# bar_graph_meter_2in_clip_in_w_47uF.net
KiCad netlist of a schematic drawn in EAGLE
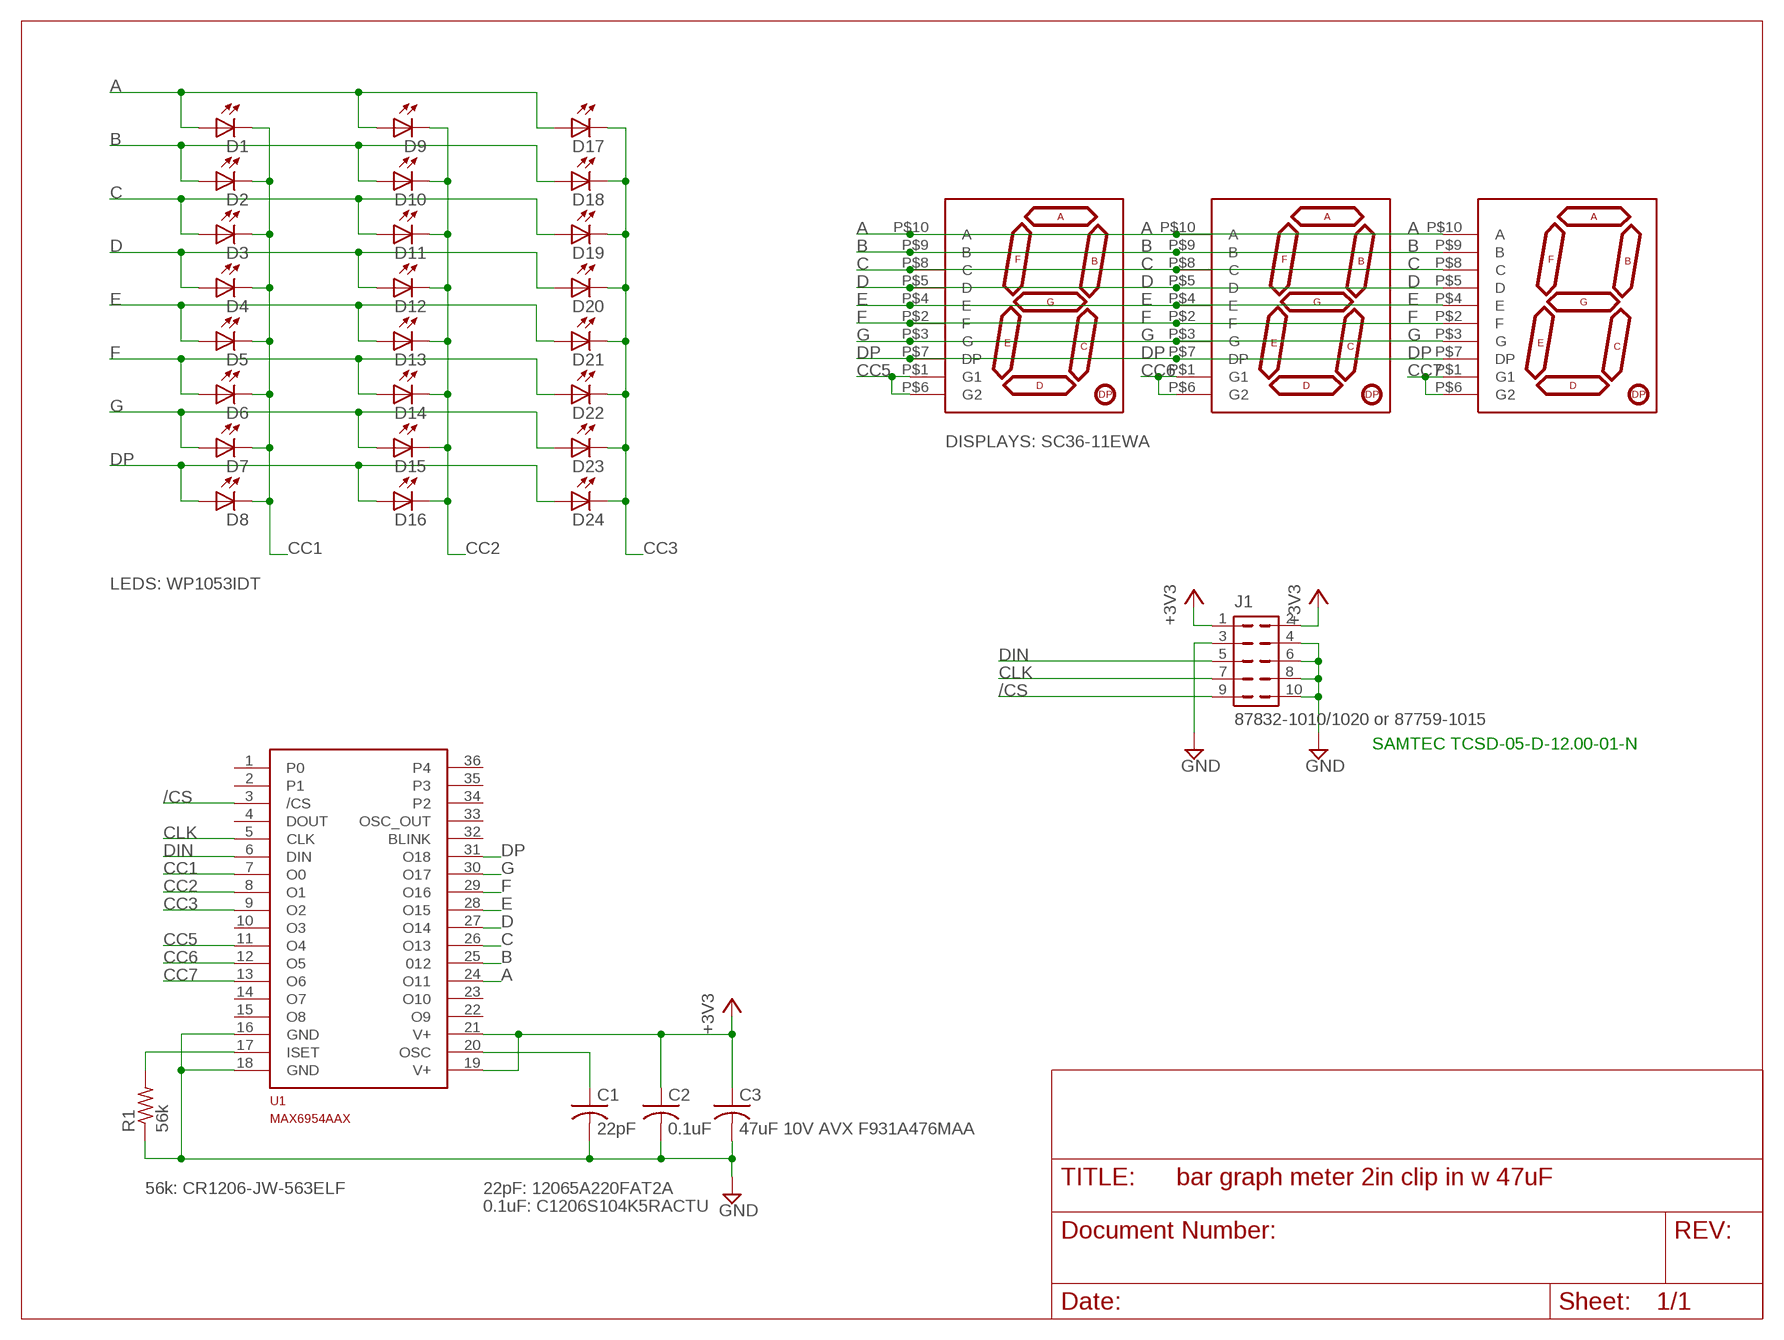
[diagram p0: schematic, sheet 1]

(export (version "E")
  (design (tool "Eeschema 10.0.6"))
  (components
    (comp (ref "C1")
      (value "22pF")
      (footprint "eagle-import:C1206")
      (libsource (lib "eagle-import") (part "C-USC1206"))
    )
    (comp (ref "C2")
      (value "0.1uF")
      (footprint "eagle-import:C1206")
      (libsource (lib "eagle-import") (part "C-USC1206"))
    )
    (comp (ref "C3")
      (value "47uF 10V AVX F931A476MAA")
      (footprint "eagle-import:C1206")
      (libsource (lib "eagle-import") (part "C-USC1206"))
    )
    (comp (ref "D1")
      (value "LEDSQR2X5")
      (footprint "eagle-import:LED2X5")
      (libsource (lib "eagle-import") (part "LEDSQR2X5"))
    )
    (comp (ref "D2")
      (value "LEDSQR2X5")
      (footprint "eagle-import:LED2X5")
      (libsource (lib "eagle-import") (part "LEDSQR2X5"))
    )
    (comp (ref "D3")
      (value "LEDSQR2X5")
      (footprint "eagle-import:LED2X5")
      (libsource (lib "eagle-import") (part "LEDSQR2X5"))
    )
    (comp (ref "D4")
      (value "LEDSQR2X5")
      (footprint "eagle-import:LED2X5")
      (libsource (lib "eagle-import") (part "LEDSQR2X5"))
    )
    (comp (ref "D5")
      (value "LEDSQR2X5")
      (footprint "eagle-import:LED2X5")
      (libsource (lib "eagle-import") (part "LEDSQR2X5"))
    )
    (comp (ref "D6")
      (value "LEDSQR2X5")
      (footprint "eagle-import:LED2X5")
      (libsource (lib "eagle-import") (part "LEDSQR2X5"))
    )
    (comp (ref "D7")
      (value "LEDSQR2X5")
      (footprint "eagle-import:LED2X5")
      (libsource (lib "eagle-import") (part "LEDSQR2X5"))
    )
    (comp (ref "D8")
      (value "LEDSQR2X5")
      (footprint "eagle-import:LED2X5")
      (libsource (lib "eagle-import") (part "LEDSQR2X5"))
    )
    (comp (ref "D9")
      (value "LEDSQR2X5")
      (footprint "eagle-import:LED2X5")
      (libsource (lib "eagle-import") (part "LEDSQR2X5"))
    )
    (comp (ref "D10")
      (value "LEDSQR2X5")
      (footprint "eagle-import:LED2X5")
      (libsource (lib "eagle-import") (part "LEDSQR2X5"))
    )
    (comp (ref "D11")
      (value "LEDSQR2X5")
      (footprint "eagle-import:LED2X5")
      (libsource (lib "eagle-import") (part "LEDSQR2X5"))
    )
    (comp (ref "D12")
      (value "LEDSQR2X5")
      (footprint "eagle-import:LED2X5")
      (libsource (lib "eagle-import") (part "LEDSQR2X5"))
    )
    (comp (ref "D13")
      (value "LEDSQR2X5")
      (footprint "eagle-import:LED2X5")
      (libsource (lib "eagle-import") (part "LEDSQR2X5"))
    )
    (comp (ref "D14")
      (value "LEDSQR2X5")
      (footprint "eagle-import:LED2X5")
      (libsource (lib "eagle-import") (part "LEDSQR2X5"))
    )
    (comp (ref "D15")
      (value "LEDSQR2X5")
      (footprint "eagle-import:LED2X5")
      (libsource (lib "eagle-import") (part "LEDSQR2X5"))
    )
    (comp (ref "D16")
      (value "LEDSQR2X5")
      (footprint "eagle-import:LED2X5")
      (libsource (lib "eagle-import") (part "LEDSQR2X5"))
    )
    (comp (ref "D17")
      (value "LEDSQR2X5")
      (footprint "eagle-import:LED2X5")
      (libsource (lib "eagle-import") (part "LEDSQR2X5"))
    )
    (comp (ref "D18")
      (value "LEDSQR2X5")
      (footprint "eagle-import:LED2X5")
      (libsource (lib "eagle-import") (part "LEDSQR2X5"))
    )
    (comp (ref "D19")
      (value "LEDSQR2X5")
      (footprint "eagle-import:LED2X5")
      (libsource (lib "eagle-import") (part "LEDSQR2X5"))
    )
    (comp (ref "D20")
      (value "LEDSQR2X5")
      (footprint "eagle-import:LED2X5")
      (libsource (lib "eagle-import") (part "LEDSQR2X5"))
    )
    (comp (ref "D21")
      (value "LEDSQR2X5")
      (footprint "eagle-import:LED2X5")
      (libsource (lib "eagle-import") (part "LEDSQR2X5"))
    )
    (comp (ref "D22")
      (value "LEDSQR2X5")
      (footprint "eagle-import:LED2X5")
      (libsource (lib "eagle-import") (part "LEDSQR2X5"))
    )
    (comp (ref "D23")
      (value "LEDSQR2X5")
      (footprint "eagle-import:LED2X5")
      (libsource (lib "eagle-import") (part "LEDSQR2X5"))
    )
    (comp (ref "D24")
      (value "LEDSQR2X5")
      (footprint "eagle-import:LED2X5")
      (libsource (lib "eagle-import") (part "LEDSQR2X5"))
    )
    (comp (ref "D25")
      (value "SC36-11EWA")
      (footprint "eagle-import:SA36-11")
      (libsource (lib "eagle-import") (part "SA36-11EWA"))
    )
    (comp (ref "D26")
      (value "SC36-11EWA")
      (footprint "eagle-import:SA36-11")
      (libsource (lib "eagle-import") (part "SA36-11EWA"))
    )
    (comp (ref "D27")
      (value "SC36-11EWA")
      (footprint "eagle-import:SA36-11")
      (libsource (lib "eagle-import") (part "SA36-11EWA"))
    )
    (comp (ref "J1")
      (value "87832-1010/1020 or 87759-1015")
      (footprint "eagle-import:87832-10")
      (libsource (lib "eagle-import") (part "87832-10"))
    )
    (comp (ref "R1")
      (value "56k")
      (footprint "eagle-import:R1206")
      (libsource (lib "eagle-import") (part "R-US_R1206"))
    )
    (comp (ref "U1")
      (value "MAX6954AAX")
      (footprint "eagle-import:MAXIM-0.8-SSOP36")
      (libsource (lib "eagle-import") (part "MAX6954AAX"))
    )
  )
  (nets
    (net (code "1") (name "+3V3") (class "Default")
      (node (ref "C2") (pin "1") (pinfunction "1_1") (pintype "passive"))
      (node (ref "C3") (pin "1") (pinfunction "1_1") (pintype "passive"))
      (node (ref "J1") (pin "1") (pinfunction "1_1") (pintype "passive"))
      (node (ref "J1") (pin "2") (pinfunction "2_2") (pintype "passive"))
      (node (ref "U1") (pin "19") (pinfunction "V+_19") (pintype "bidirectional"))
      (node (ref "U1") (pin "21") (pinfunction "V+_21") (pintype "bidirectional"))
    )
    (net (code "2") (name "/A") (class "Default")
      (node (ref "D1") (pin "A") (pinfunction "A_A") (pintype "passive"))
      (node (ref "D17") (pin "A") (pinfunction "A_A") (pintype "passive"))
      (node (ref "D25") (pin "P$10") (pinfunction "A_P$10") (pintype "bidirectional"))
      (node (ref "D26") (pin "P$10") (pinfunction "A_P$10") (pintype "bidirectional"))
      (node (ref "D27") (pin "P$10") (pinfunction "A_P$10") (pintype "bidirectional"))
      (node (ref "D9") (pin "A") (pinfunction "A_A") (pintype "passive"))
      (node (ref "U1") (pin "24") (pinfunction "O11_24") (pintype "bidirectional"))
    )
    (net (code "3") (name "/B") (class "Default")
      (node (ref "D10") (pin "A") (pinfunction "A_A") (pintype "passive"))
      (node (ref "D18") (pin "A") (pinfunction "A_A") (pintype "passive"))
      (node (ref "D2") (pin "A") (pinfunction "A_A") (pintype "passive"))
      (node (ref "D25") (pin "P$9") (pinfunction "B_P$9") (pintype "bidirectional"))
      (node (ref "D26") (pin "P$9") (pinfunction "B_P$9") (pintype "bidirectional"))
      (node (ref "D27") (pin "P$9") (pinfunction "B_P$9") (pintype "bidirectional"))
      (node (ref "U1") (pin "25") (pinfunction "012_25") (pintype "bidirectional"))
    )
    (net (code "4") (name "/C") (class "Default")
      (node (ref "D11") (pin "A") (pinfunction "A_A") (pintype "passive"))
      (node (ref "D19") (pin "A") (pinfunction "A_A") (pintype "passive"))
      (node (ref "D25") (pin "P$8") (pinfunction "C_P$8") (pintype "bidirectional"))
      (node (ref "D26") (pin "P$8") (pinfunction "C_P$8") (pintype "bidirectional"))
      (node (ref "D27") (pin "P$8") (pinfunction "C_P$8") (pintype "bidirectional"))
      (node (ref "D3") (pin "A") (pinfunction "A_A") (pintype "passive"))
      (node (ref "U1") (pin "26") (pinfunction "O13_26") (pintype "bidirectional"))
    )
    (net (code "5") (name "/CC1") (class "Default")
      (node (ref "D1") (pin "K") (pinfunction "C_K") (pintype "passive"))
      (node (ref "D2") (pin "K") (pinfunction "C_K") (pintype "passive"))
      (node (ref "D3") (pin "K") (pinfunction "C_K") (pintype "passive"))
      (node (ref "D4") (pin "K") (pinfunction "C_K") (pintype "passive"))
      (node (ref "D5") (pin "K") (pinfunction "C_K") (pintype "passive"))
      (node (ref "D6") (pin "K") (pinfunction "C_K") (pintype "passive"))
      (node (ref "D7") (pin "K") (pinfunction "C_K") (pintype "passive"))
      (node (ref "D8") (pin "K") (pinfunction "C_K") (pintype "passive"))
      (node (ref "U1") (pin "7") (pinfunction "O0_7") (pintype "bidirectional"))
    )
    (net (code "6") (name "/CC2") (class "Default")
      (node (ref "D10") (pin "K") (pinfunction "C_K") (pintype "passive"))
      (node (ref "D11") (pin "K") (pinfunction "C_K") (pintype "passive"))
      (node (ref "D12") (pin "K") (pinfunction "C_K") (pintype "passive"))
      (node (ref "D13") (pin "K") (pinfunction "C_K") (pintype "passive"))
      (node (ref "D14") (pin "K") (pinfunction "C_K") (pintype "passive"))
      (node (ref "D15") (pin "K") (pinfunction "C_K") (pintype "passive"))
      (node (ref "D16") (pin "K") (pinfunction "C_K") (pintype "passive"))
      (node (ref "D9") (pin "K") (pinfunction "C_K") (pintype "passive"))
      (node (ref "U1") (pin "8") (pinfunction "O1_8") (pintype "bidirectional"))
    )
    (net (code "7") (name "/CC3") (class "Default")
      (node (ref "D17") (pin "K") (pinfunction "C_K") (pintype "passive"))
      (node (ref "D18") (pin "K") (pinfunction "C_K") (pintype "passive"))
      (node (ref "D19") (pin "K") (pinfunction "C_K") (pintype "passive"))
      (node (ref "D20") (pin "K") (pinfunction "C_K") (pintype "passive"))
      (node (ref "D21") (pin "K") (pinfunction "C_K") (pintype "passive"))
      (node (ref "D22") (pin "K") (pinfunction "C_K") (pintype "passive"))
      (node (ref "D23") (pin "K") (pinfunction "C_K") (pintype "passive"))
      (node (ref "D24") (pin "K") (pinfunction "C_K") (pintype "passive"))
      (node (ref "U1") (pin "9") (pinfunction "O2_9") (pintype "bidirectional"))
    )
    (net (code "8") (name "/CC5") (class "Default")
      (node (ref "D25") (pin "P$1") (pinfunction "G1_P$1") (pintype "bidirectional"))
      (node (ref "D25") (pin "P$6") (pinfunction "G2_P$6") (pintype "bidirectional"))
      (node (ref "U1") (pin "11") (pinfunction "O4_11") (pintype "bidirectional"))
    )
    (net (code "9") (name "/CC6") (class "Default")
      (node (ref "D26") (pin "P$1") (pinfunction "G1_P$1") (pintype "bidirectional"))
      (node (ref "D26") (pin "P$6") (pinfunction "G2_P$6") (pintype "bidirectional"))
      (node (ref "U1") (pin "12") (pinfunction "O5_12") (pintype "bidirectional"))
    )
    (net (code "10") (name "/CC7") (class "Default")
      (node (ref "D27") (pin "P$1") (pinfunction "G1_P$1") (pintype "bidirectional"))
      (node (ref "D27") (pin "P$6") (pinfunction "G2_P$6") (pintype "bidirectional"))
      (node (ref "U1") (pin "13") (pinfunction "O6_13") (pintype "bidirectional"))
    )
    (net (code "11") (name "/CLK") (class "Default")
      (node (ref "J1") (pin "7") (pinfunction "7_7") (pintype "passive"))
      (node (ref "U1") (pin "5") (pinfunction "CLK_5") (pintype "bidirectional"))
    )
    (net (code "12") (name "/D") (class "Default")
      (node (ref "D12") (pin "A") (pinfunction "A_A") (pintype "passive"))
      (node (ref "D20") (pin "A") (pinfunction "A_A") (pintype "passive"))
      (node (ref "D25") (pin "P$5") (pinfunction "D_P$5") (pintype "bidirectional"))
      (node (ref "D26") (pin "P$5") (pinfunction "D_P$5") (pintype "bidirectional"))
      (node (ref "D27") (pin "P$5") (pinfunction "D_P$5") (pintype "bidirectional"))
      (node (ref "D4") (pin "A") (pinfunction "A_A") (pintype "passive"))
      (node (ref "U1") (pin "27") (pinfunction "O14_27") (pintype "bidirectional"))
    )
    (net (code "13") (name "/DIN") (class "Default")
      (node (ref "J1") (pin "5") (pinfunction "5_5") (pintype "passive"))
      (node (ref "U1") (pin "6") (pinfunction "DIN_6") (pintype "bidirectional"))
    )
    (net (code "14") (name "/DP") (class "Default")
      (node (ref "D16") (pin "A") (pinfunction "A_A") (pintype "passive"))
      (node (ref "D24") (pin "A") (pinfunction "A_A") (pintype "passive"))
      (node (ref "D25") (pin "P$7") (pinfunction "DP_P$7") (pintype "bidirectional"))
      (node (ref "D26") (pin "P$7") (pinfunction "DP_P$7") (pintype "bidirectional"))
      (node (ref "D27") (pin "P$7") (pinfunction "DP_P$7") (pintype "bidirectional"))
      (node (ref "D8") (pin "A") (pinfunction "A_A") (pintype "passive"))
      (node (ref "U1") (pin "31") (pinfunction "O18_31") (pintype "bidirectional"))
    )
    (net (code "15") (name "/E") (class "Default")
      (node (ref "D13") (pin "A") (pinfunction "A_A") (pintype "passive"))
      (node (ref "D21") (pin "A") (pinfunction "A_A") (pintype "passive"))
      (node (ref "D25") (pin "P$4") (pinfunction "E_P$4") (pintype "bidirectional"))
      (node (ref "D26") (pin "P$4") (pinfunction "E_P$4") (pintype "bidirectional"))
      (node (ref "D27") (pin "P$4") (pinfunction "E_P$4") (pintype "bidirectional"))
      (node (ref "D5") (pin "A") (pinfunction "A_A") (pintype "passive"))
      (node (ref "U1") (pin "28") (pinfunction "O15_28") (pintype "bidirectional"))
    )
    (net (code "16") (name "/F") (class "Default")
      (node (ref "D14") (pin "A") (pinfunction "A_A") (pintype "passive"))
      (node (ref "D22") (pin "A") (pinfunction "A_A") (pintype "passive"))
      (node (ref "D25") (pin "P$2") (pinfunction "F_P$2") (pintype "bidirectional"))
      (node (ref "D26") (pin "P$2") (pinfunction "F_P$2") (pintype "bidirectional"))
      (node (ref "D27") (pin "P$2") (pinfunction "F_P$2") (pintype "bidirectional"))
      (node (ref "D6") (pin "A") (pinfunction "A_A") (pintype "passive"))
      (node (ref "U1") (pin "29") (pinfunction "O16_29") (pintype "bidirectional"))
    )
    (net (code "17") (name "/G") (class "Default")
      (node (ref "D15") (pin "A") (pinfunction "A_A") (pintype "passive"))
      (node (ref "D23") (pin "A") (pinfunction "A_A") (pintype "passive"))
      (node (ref "D25") (pin "P$3") (pinfunction "G_P$3") (pintype "bidirectional"))
      (node (ref "D26") (pin "P$3") (pinfunction "G_P$3") (pintype "bidirectional"))
      (node (ref "D27") (pin "P$3") (pinfunction "G_P$3") (pintype "bidirectional"))
      (node (ref "D7") (pin "A") (pinfunction "A_A") (pintype "passive"))
      (node (ref "U1") (pin "30") (pinfunction "O17_30") (pintype "bidirectional"))
    )
    (net (code "18") (name "/{slash}CS") (class "Default")
      (node (ref "J1") (pin "9") (pinfunction "9_9") (pintype "passive"))
      (node (ref "U1") (pin "3") (pinfunction "/CS_3") (pintype "bidirectional"))
    )
    (net (code "19") (name "GND") (class "Default")
      (node (ref "C1") (pin "2") (pinfunction "2_2") (pintype "passive"))
      (node (ref "C2") (pin "2") (pinfunction "2_2") (pintype "passive"))
      (node (ref "C3") (pin "2") (pinfunction "2_2") (pintype "passive"))
      (node (ref "J1") (pin "10") (pinfunction "10_10") (pintype "passive"))
      (node (ref "J1") (pin "3") (pinfunction "3_3") (pintype "passive"))
      (node (ref "J1") (pin "4") (pinfunction "4_4") (pintype "passive"))
      (node (ref "J1") (pin "6") (pinfunction "6_6") (pintype "passive"))
      (node (ref "J1") (pin "8") (pinfunction "8_8") (pintype "passive"))
      (node (ref "R1") (pin "1") (pinfunction "1_1") (pintype "passive"))
      (node (ref "U1") (pin "16") (pinfunction "GND_16") (pintype "bidirectional"))
      (node (ref "U1") (pin "18") (pinfunction "GND_18") (pintype "bidirectional"))
    )
    (net (code "20") (name "Net-(U1-ISET)") (class "Default")
      (node (ref "R1") (pin "2") (pinfunction "2_2") (pintype "passive"))
      (node (ref "U1") (pin "17") (pinfunction "ISET_17") (pintype "bidirectional"))
    )
    (net (code "21") (name "Net-(U1-OSC)") (class "Default")
      (node (ref "C1") (pin "1") (pinfunction "1_1") (pintype "passive"))
      (node (ref "U1") (pin "20") (pinfunction "OSC_20") (pintype "bidirectional"))
    )
    (net (code "22") (name "unconnected-(U1-BLINK-Pad32)") (class "Default")
      (node (ref "U1") (pin "32") (pinfunction "BLINK_32") (pintype "bidirectional"))
    )
    (net (code "23") (name "unconnected-(U1-DOUT-Pad4)") (class "Default")
      (node (ref "U1") (pin "4") (pinfunction "DOUT_4") (pintype "bidirectional"))
    )
    (net (code "24") (name "unconnected-(U1-O3-Pad10)") (class "Default")
      (node (ref "U1") (pin "10") (pinfunction "O3_10") (pintype "bidirectional"))
    )
    (net (code "25") (name "unconnected-(U1-O7-Pad14)") (class "Default")
      (node (ref "U1") (pin "14") (pinfunction "O7_14") (pintype "bidirectional"))
    )
    (net (code "26") (name "unconnected-(U1-O8-Pad15)") (class "Default")
      (node (ref "U1") (pin "15") (pinfunction "O8_15") (pintype "bidirectional"))
    )
    (net (code "27") (name "unconnected-(U1-O9-Pad22)") (class "Default")
      (node (ref "U1") (pin "22") (pinfunction "O9_22") (pintype "bidirectional"))
    )
    (net (code "28") (name "unconnected-(U1-O10-Pad23)") (class "Default")
      (node (ref "U1") (pin "23") (pinfunction "O10_23") (pintype "bidirectional"))
    )
    (net (code "29") (name "unconnected-(U1-OSC_OUT-Pad33)") (class "Default")
      (node (ref "U1") (pin "33") (pinfunction "OSC_OUT_33") (pintype "bidirectional"))
    )
    (net (code "30") (name "unconnected-(U1-P0-Pad1)") (class "Default")
      (node (ref "U1") (pin "1") (pinfunction "P0_1") (pintype "bidirectional"))
    )
    (net (code "31") (name "unconnected-(U1-P1-Pad2)") (class "Default")
      (node (ref "U1") (pin "2") (pinfunction "P1_2") (pintype "bidirectional"))
    )
    (net (code "32") (name "unconnected-(U1-P2-Pad34)") (class "Default")
      (node (ref "U1") (pin "34") (pinfunction "P2_34") (pintype "bidirectional"))
    )
    (net (code "33") (name "unconnected-(U1-P3-Pad35)") (class "Default")
      (node (ref "U1") (pin "35") (pinfunction "P3_35") (pintype "bidirectional"))
    )
    (net (code "34") (name "unconnected-(U1-P4-Pad36)") (class "Default")
      (node (ref "U1") (pin "36") (pinfunction "P4_36") (pintype "bidirectional"))
    )
  )
)
